# ethernet_hdmi.net
KiCad netlist of a schematic drawn in Altium Designer
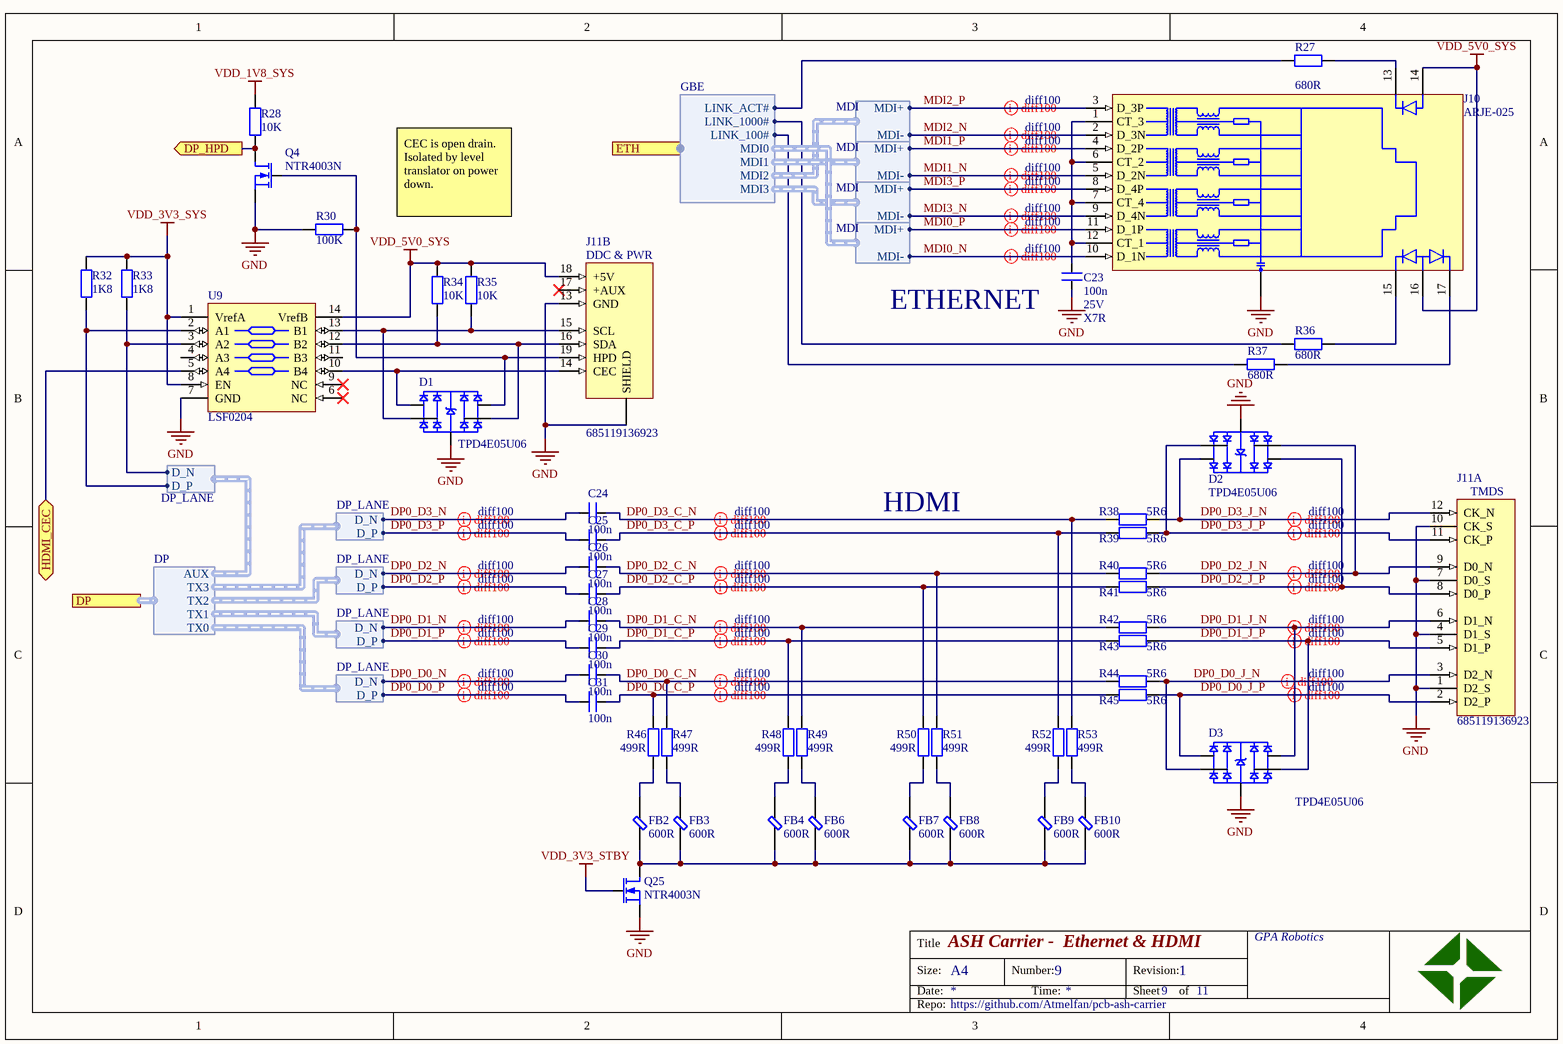
[diagram p0: ethernet_hdmi.SchDoc]

(export (version "E")
  (design (tool "Eeschema 10.0.6"))
  (components
    (comp (ref "C23")
      (value "100n")
      (footprint "C1005[0402]")
      (description "Capacitor")
      (fields (field (name "VOLTAGE") "25V") (field (name "TYPE") "X7R") (field (name "Comment") "cap"))
      (libsource (lib "gpa_passives") (part "cap"))
    )
    (comp (ref "C24")
      (value "100n")
      (footprint "C1005[0402]")
      (description "Capacitor")
      (fields (field (name "VOLTAGE") "25V") (field (name "Comment") "cap"))
      (libsource (lib "gpa_passives") (part "cap"))
    )
    (comp (ref "C25")
      (value "100n")
      (footprint "C1005[0402]")
      (description "Capacitor")
      (fields (field (name "VOLTAGE") "25V") (field (name "Comment") "cap"))
      (libsource (lib "gpa_passives") (part "cap"))
    )
    (comp (ref "C26")
      (value "100n")
      (footprint "C1005[0402]")
      (description "Capacitor")
      (fields (field (name "VOLTAGE") "25V") (field (name "Comment") "cap"))
      (libsource (lib "gpa_passives") (part "cap"))
    )
    (comp (ref "C27")
      (value "100n")
      (footprint "C1005[0402]")
      (description "Capacitor")
      (fields (field (name "VOLTAGE") "25V") (field (name "Comment") "cap"))
      (libsource (lib "gpa_passives") (part "cap"))
    )
    (comp (ref "C28")
      (value "100n")
      (footprint "C1005[0402]")
      (description "Capacitor")
      (fields (field (name "VOLTAGE") "25V") (field (name "Comment") "cap"))
      (libsource (lib "gpa_passives") (part "cap"))
    )
    (comp (ref "C29")
      (value "100n")
      (footprint "C1005[0402]")
      (description "Capacitor")
      (fields (field (name "VOLTAGE") "25V") (field (name "Comment") "cap"))
      (libsource (lib "gpa_passives") (part "cap"))
    )
    (comp (ref "C30")
      (value "100n")
      (footprint "C1005[0402]")
      (description "Capacitor")
      (fields (field (name "VOLTAGE") "25V") (field (name "Comment") "cap"))
      (libsource (lib "gpa_passives") (part "cap"))
    )
    (comp (ref "C31")
      (value "100n")
      (footprint "C1005[0402]")
      (description "Capacitor")
      (fields (field (name "VOLTAGE") "25V") (field (name "Comment") "cap"))
      (libsource (lib "gpa_passives") (part "cap"))
    )
    (comp (ref "D1")
      (value "TPD4E05U06")
      (footprint "TI_PSON50P100X55-10N")
      (libsource (lib "gpa_ti") (part "tpd4e05u06"))
    )
    (comp (ref "D2")
      (value "TPD4E05U06")
      (footprint "TI_PSON50P100X55-10N")
      (libsource (lib "gpa_ti") (part "tpd4e05u06"))
    )
    (comp (ref "D3")
      (value "TPD4E05U06")
      (footprint "TI_PSON50P100X55-10N")
      (libsource (lib "gpa_ti") (part "tpd4e05u06"))
    )
    (comp (ref "FB2")
      (value "600R")
      (footprint "FBC1005X06N")
      (description "Ferrite bead")
      (libsource (lib "gpa_passives") (part "ferrite_bead"))
    )
    (comp (ref "FB3")
      (value "600R")
      (footprint "FBC1005X06N")
      (description "Ferrite bead")
      (libsource (lib "gpa_passives") (part "ferrite_bead"))
    )
    (comp (ref "FB4")
      (value "600R")
      (footprint "FBC1005X06N")
      (description "Ferrite bead")
      (libsource (lib "gpa_passives") (part "ferrite_bead"))
    )
    (comp (ref "FB6")
      (value "600R")
      (footprint "FBC1005X06N")
      (description "Ferrite bead")
      (libsource (lib "gpa_passives") (part "ferrite_bead"))
    )
    (comp (ref "FB7")
      (value "600R")
      (footprint "FBC1005X06N")
      (description "Ferrite bead")
      (libsource (lib "gpa_passives") (part "ferrite_bead"))
    )
    (comp (ref "FB8")
      (value "600R")
      (footprint "FBC1005X06N")
      (description "Ferrite bead")
      (libsource (lib "gpa_passives") (part "ferrite_bead"))
    )
    (comp (ref "FB9")
      (value "600R")
      (footprint "FBC1005X06N")
      (description "Ferrite bead")
      (libsource (lib "gpa_passives") (part "ferrite_bead"))
    )
    (comp (ref "FB10")
      (value "600R")
      (footprint "FBC1005X06N")
      (description "Ferrite bead")
      (libsource (lib "gpa_passives") (part "ferrite_bead"))
    )
    (comp (ref "J10")
      (value "ARJE-025")
      (footprint "abraconn_rj45_arje0025")
      (description "RJ45 with integrated magnetics")
      (libsource (lib "gpa_connectors") (part "geth_wmagnetics"))
    )
    (comp (ref "J11")
      (value "685119136923")
      (footprint "wurth_hdmi_mini")
      (libsource (lib "gpa_connectors") (part "hdmi_mini_c"))
    )
    (comp (ref "Q4")
      (value "NTR4003N")
      (footprint "NCH_SOT95P237X110-3N")
      (libsource (lib "gpa_actives") (part "nch_mosfet"))
    )
    (comp (ref "Q25")
      (value "NTR4003N")
      (footprint "NCH_SOT95P237X110-3N")
      (libsource (lib "gpa_actives") (part "nch_mosfet"))
    )
    (comp (ref "R27")
      (value "680R")
      (footprint "R1005[0402]")
      (description "Resistor")
      (fields (field (name "Comment") "res"))
      (libsource (lib "") (part "res_2"))
    )
    (comp (ref "R28")
      (value "10K")
      (footprint "R1005[0402]")
      (description "Resistor")
      (fields (field (name "Comment") "res"))
      (libsource (lib "") (part "res_1"))
    )
    (comp (ref "R30")
      (value "100K")
      (footprint "R1005[0402]")
      (description "Resistor")
      (fields (field (name "Comment") "res"))
      (libsource (lib "") (part "res_2"))
    )
    (comp (ref "R32")
      (value "1K8")
      (footprint "R1005[0402]")
      (description "Resistor")
      (fields (field (name "Comment") "res"))
      (libsource (lib "") (part "res_1"))
    )
    (comp (ref "R33")
      (value "1K8")
      (footprint "R1005[0402]")
      (description "Resistor")
      (fields (field (name "Comment") "res"))
      (libsource (lib "") (part "res_1"))
    )
    (comp (ref "R34")
      (value "10K")
      (footprint "R1005[0402]")
      (description "Resistor")
      (fields (field (name "Comment") "res"))
      (libsource (lib "") (part "res_1"))
    )
    (comp (ref "R35")
      (value "10K")
      (footprint "R1005[0402]")
      (description "Resistor")
      (fields (field (name "Comment") "res"))
      (libsource (lib "") (part "res_1"))
    )
    (comp (ref "R36")
      (value "680R")
      (footprint "R1005[0402]")
      (description "Resistor")
      (fields (field (name "Comment") "res"))
      (libsource (lib "gpa_passives") (part "res"))
    )
    (comp (ref "R37")
      (value "680R")
      (footprint "R1005[0402]")
      (description "Resistor")
      (fields (field (name "Comment") "res"))
      (libsource (lib "") (part "res_2"))
    )
    (comp (ref "R38")
      (value "5R6")
      (footprint "R1005[0402]")
      (description "Resistor")
      (fields (field (name "Comment") "res"))
      (libsource (lib "gpa_passives") (part "res"))
    )
    (comp (ref "R39")
      (value "5R6")
      (footprint "R1005[0402]")
      (description "Resistor")
      (fields (field (name "Comment") "res"))
      (libsource (lib "gpa_passives") (part "res"))
    )
    (comp (ref "R40")
      (value "5R6")
      (footprint "R1005[0402]")
      (description "Resistor")
      (fields (field (name "Comment") "res"))
      (libsource (lib "gpa_passives") (part "res"))
    )
    (comp (ref "R41")
      (value "5R6")
      (footprint "R1005[0402]")
      (description "Resistor")
      (fields (field (name "Comment") "res"))
      (libsource (lib "gpa_passives") (part "res"))
    )
    (comp (ref "R42")
      (value "5R6")
      (footprint "R1005[0402]")
      (description "Resistor")
      (fields (field (name "Comment") "res"))
      (libsource (lib "gpa_passives") (part "res"))
    )
    (comp (ref "R43")
      (value "5R6")
      (footprint "R1005[0402]")
      (description "Resistor")
      (fields (field (name "Comment") "res"))
      (libsource (lib "gpa_passives") (part "res"))
    )
    (comp (ref "R44")
      (value "5R6")
      (footprint "R1005[0402]")
      (description "Resistor")
      (fields (field (name "Comment") "res"))
      (libsource (lib "gpa_passives") (part "res"))
    )
    (comp (ref "R45")
      (value "5R6")
      (footprint "R1005[0402]")
      (description "Resistor")
      (fields (field (name "Comment") "res"))
      (libsource (lib "gpa_passives") (part "res"))
    )
    (comp (ref "R46")
      (value "499R")
      (footprint "R1005[0402]")
      (description "Resistor")
      (fields (field (name "Comment") "res"))
      (libsource (lib "") (part "res_1"))
    )
    (comp (ref "R47")
      (value "499R")
      (footprint "R1005[0402]")
      (description "Resistor")
      (fields (field (name "Comment") "res"))
      (libsource (lib "") (part "res_1"))
    )
    (comp (ref "R48")
      (value "499R")
      (footprint "R1005[0402]")
      (description "Resistor")
      (fields (field (name "Comment") "res"))
      (libsource (lib "") (part "res_1"))
    )
    (comp (ref "R49")
      (value "499R")
      (footprint "R1005[0402]")
      (description "Resistor")
      (fields (field (name "Comment") "res"))
      (libsource (lib "") (part "res_1"))
    )
    (comp (ref "R50")
      (value "499R")
      (footprint "R1005[0402]")
      (description "Resistor")
      (fields (field (name "Comment") "res"))
      (libsource (lib "") (part "res_1"))
    )
    (comp (ref "R51")
      (value "499R")
      (footprint "R1005[0402]")
      (description "Resistor")
      (fields (field (name "Comment") "res"))
      (libsource (lib "") (part "res_1"))
    )
    (comp (ref "R52")
      (value "499R")
      (footprint "R1005[0402]")
      (description "Resistor")
      (fields (field (name "Comment") "res"))
      (libsource (lib "") (part "res_1"))
    )
    (comp (ref "R53")
      (value "499R")
      (footprint "R1005[0402]")
      (description "Resistor")
      (fields (field (name "Comment") "res"))
      (libsource (lib "") (part "res_1"))
    )
    (comp (ref "U9")
      (value "LSF0204")
      (footprint "TI_TSOP65P640X120-14N")
      (libsource (lib "gpa_ti") (part "lsf0204"))
    )
  )
  (nets
    (net (code "5") (name "/DP0_D0_C_N") (class "Default")
      (node (ref "C30") (pin "1") (pinfunction "1_1") (pintype "passive"))
      (node (ref "R44") (pin "1") (pinfunction "1_1") (pintype "passive"))
      (node (ref "R47") (pin "2") (pinfunction "2_2") (pintype "passive"))
    )
    (net (code "6") (name "/DP0_D0_C_P") (class "Default")
      (node (ref "C31") (pin "1") (pinfunction "1_1") (pintype "passive"))
      (node (ref "R45") (pin "1") (pinfunction "1_1") (pintype "passive"))
      (node (ref "R46") (pin "2") (pinfunction "2_2") (pintype "passive"))
    )
    (net (code "7") (name "/DP0_D0_J_N") (class "Default")
      (node (ref "D3") (pin "4") (pinfunction "D2-_4") (pintype "passive"))
      (node (ref "J11") (pin "3") (pinfunction "D2_N_3") (pintype "input"))
      (node (ref "R44") (pin "2") (pinfunction "2_2") (pintype "passive"))
    )
    (net (code "8") (name "/DP0_D0_J_P") (class "Default")
      (node (ref "D3") (pin "5") (pinfunction "D2+_5") (pintype "passive"))
      (node (ref "J11") (pin "2") (pinfunction "D2_P_2") (pintype "input"))
      (node (ref "R45") (pin "2") (pinfunction "2_2") (pintype "passive"))
    )
    (net (code "9") (name "/DP0_D0_N") (class "Default")
      (node (ref "C30") (pin "2") (pinfunction "2_2") (pintype "passive"))
    )
    (net (code "10") (name "/DP0_D0_P") (class "Default")
      (node (ref "C31") (pin "2") (pinfunction "2_2") (pintype "passive"))
    )
    (net (code "11") (name "/DP0_D1_C_N") (class "Default")
      (node (ref "C28") (pin "1") (pinfunction "1_1") (pintype "passive"))
      (node (ref "R42") (pin "1") (pinfunction "1_1") (pintype "passive"))
      (node (ref "R49") (pin "2") (pinfunction "2_2") (pintype "passive"))
    )
    (net (code "12") (name "/DP0_D1_C_P") (class "Default")
      (node (ref "C29") (pin "1") (pinfunction "1_1") (pintype "passive"))
      (node (ref "R43") (pin "1") (pinfunction "1_1") (pintype "passive"))
      (node (ref "R48") (pin "2") (pinfunction "2_2") (pintype "passive"))
    )
    (net (code "13") (name "/DP0_D1_J_N") (class "Default")
      (node (ref "D3") (pin "1") (pinfunction "D1+_1") (pintype "passive"))
      (node (ref "J11") (pin "6") (pinfunction "D1_N_6") (pintype "input"))
      (node (ref "R42") (pin "2") (pinfunction "2_2") (pintype "passive"))
    )
    (net (code "14") (name "/DP0_D1_J_P") (class "Default")
      (node (ref "D3") (pin "2") (pinfunction "D1-_2") (pintype "passive"))
      (node (ref "J11") (pin "5") (pinfunction "D1_P_5") (pintype "input"))
      (node (ref "R43") (pin "2") (pinfunction "2_2") (pintype "passive"))
    )
    (net (code "15") (name "/DP0_D1_N") (class "Default")
      (node (ref "C28") (pin "2") (pinfunction "2_2") (pintype "passive"))
    )
    (net (code "16") (name "/DP0_D1_P") (class "Default")
      (node (ref "C29") (pin "2") (pinfunction "2_2") (pintype "passive"))
    )
    (net (code "17") (name "/DP0_D2_C_N") (class "Default")
      (node (ref "C26") (pin "1") (pinfunction "1_1") (pintype "passive"))
      (node (ref "R40") (pin "1") (pinfunction "1_1") (pintype "passive"))
      (node (ref "R51") (pin "2") (pinfunction "2_2") (pintype "passive"))
    )
    (net (code "18") (name "/DP0_D2_C_P") (class "Default")
      (node (ref "C27") (pin "1") (pinfunction "1_1") (pintype "passive"))
      (node (ref "R41") (pin "1") (pinfunction "1_1") (pintype "passive"))
      (node (ref "R50") (pin "2") (pinfunction "2_2") (pintype "passive"))
    )
    (net (code "19") (name "/DP0_D2_J_N") (class "Default")
      (node (ref "D2") (pin "2") (pinfunction "D1-_2") (pintype "passive"))
      (node (ref "J11") (pin "9") (pinfunction "D0_N_9") (pintype "input"))
      (node (ref "R40") (pin "2") (pinfunction "2_2") (pintype "passive"))
    )
    (net (code "20") (name "/DP0_D2_J_P") (class "Default")
      (node (ref "D2") (pin "1") (pinfunction "D1+_1") (pintype "passive"))
      (node (ref "J11") (pin "8") (pinfunction "D0_P_8") (pintype "input"))
      (node (ref "R41") (pin "2") (pinfunction "2_2") (pintype "passive"))
    )
    (net (code "21") (name "/DP0_D2_N") (class "Default")
      (node (ref "C26") (pin "2") (pinfunction "2_2") (pintype "passive"))
    )
    (net (code "22") (name "/DP0_D2_P") (class "Default")
      (node (ref "C27") (pin "2") (pinfunction "2_2") (pintype "passive"))
    )
    (net (code "23") (name "/DP0_D3_C_N") (class "Default")
      (node (ref "C24") (pin "1") (pinfunction "1_1") (pintype "passive"))
      (node (ref "R38") (pin "1") (pinfunction "1_1") (pintype "passive"))
      (node (ref "R53") (pin "2") (pinfunction "2_2") (pintype "passive"))
    )
    (net (code "24") (name "/DP0_D3_C_P") (class "Default")
      (node (ref "C25") (pin "1") (pinfunction "1_1") (pintype "passive"))
      (node (ref "R39") (pin "1") (pinfunction "1_1") (pintype "passive"))
      (node (ref "R52") (pin "2") (pinfunction "2_2") (pintype "passive"))
    )
    (net (code "25") (name "/DP0_D3_J_N") (class "Default")
      (node (ref "D2") (pin "5") (pinfunction "D2+_5") (pintype "passive"))
      (node (ref "J11") (pin "12") (pinfunction "CK_N_12") (pintype "input"))
      (node (ref "R38") (pin "2") (pinfunction "2_2") (pintype "passive"))
    )
    (net (code "26") (name "/DP0_D3_J_P") (class "Default")
      (node (ref "D2") (pin "4") (pinfunction "D2-_4") (pintype "passive"))
      (node (ref "J11") (pin "11") (pinfunction "CK_P_11") (pintype "input"))
      (node (ref "R39") (pin "2") (pinfunction "2_2") (pintype "passive"))
    )
    (net (code "27") (name "/DP0_D3_N") (class "Default")
      (node (ref "C24") (pin "2") (pinfunction "2_2") (pintype "passive"))
    )
    (net (code "28") (name "/DP0_D3_P") (class "Default")
      (node (ref "C25") (pin "2") (pinfunction "2_2") (pintype "passive"))
    )
    (net (code "29") (name "/DP_HPD") (class "Default")
      (node (ref "Q4") (pin "D") (pinfunction "D_D") (pintype "passive"))
      (node (ref "R28") (pin "1") (pinfunction "1_1") (pintype "passive"))
    )
    (net (code "32") (name "/HDMI_CEC") (class "Default")
      (node (ref "U9") (pin "5") (pinfunction "A4_5") (pintype "bidirectional"))
    )
    (net (code "33") (name "/LINK_100#") (class "Default")
      (node (ref "R37") (pin "2") (pinfunction "2_2") (pintype "passive"))
    )
    (net (code "34") (name "/LINK_1000#") (class "Default")
      (node (ref "R36") (pin "1") (pinfunction "1_1") (pintype "passive"))
    )
    (net (code "35") (name "/LINK_ACT#") (class "Default")
      (node (ref "R27") (pin "2") (pinfunction "2_2") (pintype "passive"))
    )
    (net (code "36") (name "/MDI0_N") (class "Default")
      (node (ref "J10") (pin "10") (pinfunction "D_1N_10") (pintype "input"))
    )
    (net (code "37") (name "/MDI0_P") (class "Default")
      (node (ref "J10") (pin "11") (pinfunction "D_1P_11") (pintype "input"))
    )
    (net (code "38") (name "/MDI1_N") (class "Default")
      (node (ref "J10") (pin "5") (pinfunction "D_2N_5") (pintype "input"))
    )
    (net (code "39") (name "/MDI1_P") (class "Default")
      (node (ref "J10") (pin "4") (pinfunction "D_2P_4") (pintype "input"))
    )
    (net (code "40") (name "/MDI2_N") (class "Default")
      (node (ref "J10") (pin "2") (pinfunction "D_3N_2") (pintype "input"))
    )
    (net (code "41") (name "/MDI2_P") (class "Default")
      (node (ref "J10") (pin "3") (pinfunction "D_3P_3") (pintype "input"))
    )
    (net (code "42") (name "/MDI3_N") (class "Default")
      (node (ref "J10") (pin "9") (pinfunction "D_4N_9") (pintype "input"))
    )
    (net (code "43") (name "/MDI3_P") (class "Default")
      (node (ref "J10") (pin "8") (pinfunction "D_4P_8") (pintype "input"))
    )
    (net (code "46") (name "GND") (class "Default")
      (node (ref "C23") (pin "1") (pinfunction "1_1") (pintype "passive"))
      (node (ref "D1") (pin "3") (pinfunction "GND_3") (pintype "passive"))
      (node (ref "D2") (pin "3") (pinfunction "GND_3") (pintype "passive"))
      (node (ref "D3") (pin "3") (pinfunction "GND_3") (pintype "passive"))
      (node (ref "J10") (pin "SHIELD") (pinfunction "SHIELD_SHIELD") (pintype "power_in"))
      (node (ref "J11") (pin "1") (pinfunction "D2_S_1") (pintype "power_in"))
      (node (ref "J11") (pin "10") (pinfunction "CK_S_10") (pintype "power_in"))
      (node (ref "J11") (pin "13") (pinfunction "GND_13") (pintype "input"))
      (node (ref "J11") (pin "4") (pinfunction "D1_S_4") (pintype "power_in"))
      (node (ref "J11") (pin "7") (pinfunction "D0_S_7") (pintype "power_in"))
      (node (ref "J11") (pin "SHIELD") (pinfunction "SHIELD_SHIELD") (pintype "passive"))
      (node (ref "Q25") (pin "S") (pinfunction "S_S") (pintype "passive"))
      (node (ref "Q4") (pin "S") (pinfunction "S_S") (pintype "passive"))
      (node (ref "R30") (pin "2") (pinfunction "2_2") (pintype "passive"))
      (node (ref "U9") (pin "7") (pinfunction "GND_7") (pintype "power_in"))
    )
    (net (code "47") (name "Net-(D1-D1+)") (class "Default")
      (node (ref "D1") (pin "1") (pinfunction "D1+_1") (pintype "passive"))
      (node (ref "J11") (pin "14") (pinfunction "CEC_14") (pintype "input"))
      (node (ref "U9") (pin "10") (pinfunction "B4_10") (pintype "bidirectional"))
    )
    (net (code "48") (name "Net-(D1-D1-)") (class "Default")
      (node (ref "D1") (pin "2") (pinfunction "D1-_2") (pintype "passive"))
      (node (ref "J11") (pin "15") (pinfunction "SCL_15") (pintype "input"))
      (node (ref "R35") (pin "1") (pinfunction "1_1") (pintype "passive"))
      (node (ref "U9") (pin "13") (pinfunction "B1_13") (pintype "bidirectional"))
    )
    (net (code "49") (name "Net-(D1-D2+)") (class "Default")
      (node (ref "D1") (pin "5") (pinfunction "D2+_5") (pintype "passive"))
      (node (ref "J11") (pin "19") (pinfunction "HPD_19") (pintype "input"))
      (node (ref "Q4") (pin "G") (pinfunction "G_G") (pintype "passive"))
      (node (ref "R30") (pin "1") (pinfunction "1_1") (pintype "passive"))
    )
    (net (code "50") (name "Net-(D1-D2-)") (class "Default")
      (node (ref "D1") (pin "4") (pinfunction "D2-_4") (pintype "passive"))
      (node (ref "J11") (pin "16") (pinfunction "SDA_16") (pintype "input"))
      (node (ref "R34") (pin "1") (pinfunction "1_1") (pintype "passive"))
      (node (ref "U9") (pin "12") (pinfunction "B2_12") (pintype "bidirectional"))
    )
    (net (code "51") (name "Net-(FB2-Pad2)") (class "Default")
      (node (ref "FB2") (pin "2") (pinfunction "2_2") (pintype "passive"))
      (node (ref "R46") (pin "1") (pinfunction "1_1") (pintype "passive"))
    )
    (net (code "52") (name "Net-(FB3-Pad2)") (class "Default")
      (node (ref "FB3") (pin "2") (pinfunction "2_2") (pintype "passive"))
      (node (ref "R47") (pin "1") (pinfunction "1_1") (pintype "passive"))
    )
    (net (code "53") (name "Net-(FB4-Pad2)") (class "Default")
      (node (ref "FB4") (pin "2") (pinfunction "2_2") (pintype "passive"))
      (node (ref "R48") (pin "1") (pinfunction "1_1") (pintype "passive"))
    )
    (net (code "54") (name "Net-(FB6-Pad2)") (class "Default")
      (node (ref "FB6") (pin "2") (pinfunction "2_2") (pintype "passive"))
      (node (ref "R49") (pin "1") (pinfunction "1_1") (pintype "passive"))
    )
    (net (code "55") (name "Net-(FB7-Pad2)") (class "Default")
      (node (ref "FB7") (pin "2") (pinfunction "2_2") (pintype "passive"))
      (node (ref "R50") (pin "1") (pinfunction "1_1") (pintype "passive"))
    )
    (net (code "56") (name "Net-(FB8-Pad2)") (class "Default")
      (node (ref "FB8") (pin "2") (pinfunction "2_2") (pintype "passive"))
      (node (ref "R51") (pin "1") (pinfunction "1_1") (pintype "passive"))
    )
    (net (code "57") (name "Net-(FB9-Pad2)") (class "Default")
      (node (ref "FB9") (pin "2") (pinfunction "2_2") (pintype "passive"))
      (node (ref "R52") (pin "1") (pinfunction "1_1") (pintype "passive"))
    )
    (net (code "58") (name "Net-(FB10-Pad1)") (class "Default")
      (node (ref "FB10") (pin "1") (pinfunction "1_1") (pintype "passive"))
      (node (ref "FB2") (pin "1") (pinfunction "1_1") (pintype "passive"))
      (node (ref "FB3") (pin "1") (pinfunction "1_1") (pintype "passive"))
      (node (ref "FB4") (pin "1") (pinfunction "1_1") (pintype "passive"))
      (node (ref "FB6") (pin "1") (pinfunction "1_1") (pintype "passive"))
      (node (ref "FB7") (pin "1") (pinfunction "1_1") (pintype "passive"))
      (node (ref "FB8") (pin "1") (pinfunction "1_1") (pintype "passive"))
      (node (ref "FB9") (pin "1") (pinfunction "1_1") (pintype "passive"))
      (node (ref "Q25") (pin "D") (pinfunction "D_D") (pintype "passive"))
    )
    (net (code "59") (name "Net-(FB10-Pad2)") (class "Default")
      (node (ref "FB10") (pin "2") (pinfunction "2_2") (pintype "passive"))
      (node (ref "R53") (pin "1") (pinfunction "1_1") (pintype "passive"))
    )
    (net (code "60") (name "Net-(J10-CT_1)") (class "Default")
      (node (ref "C23") (pin "2") (pinfunction "2_2") (pintype "passive"))
      (node (ref "J10") (pin "1") (pinfunction "CT_3_1") (pintype "passive"))
      (node (ref "J10") (pin "12") (pinfunction "CT_1_12") (pintype "passive"))
      (node (ref "J10") (pin "6") (pinfunction "CT_2_6") (pintype "passive"))
      (node (ref "J10") (pin "7") (pinfunction "CT_4_7") (pintype "passive"))
    )
    (net (code "61") (name "Net-(J10-Pad13)") (class "Default")
      (node (ref "J10") (pin "13") (pinfunction "13_13") (pintype "passive"))
      (node (ref "R27") (pin "1") (pinfunction "1_1") (pintype "passive"))
    )
    (net (code "62") (name "Net-(J10-Pad15)") (class "Default")
      (node (ref "J10") (pin "15") (pinfunction "15_15") (pintype "passive"))
      (node (ref "R36") (pin "2") (pinfunction "2_2") (pintype "passive"))
    )
    (net (code "63") (name "Net-(J10-Pad17)") (class "Default")
      (node (ref "J10") (pin "17") (pinfunction "17_17") (pintype "passive"))
      (node (ref "R37") (pin "1") (pinfunction "1_1") (pintype "passive"))
    )
    (net (code "64") (name "Net-(U9-A1)") (class "Default")
      (node (ref "R32") (pin "1") (pinfunction "1_1") (pintype "passive"))
      (node (ref "U9") (pin "2") (pinfunction "A1_2") (pintype "bidirectional"))
    )
    (net (code "65") (name "Net-(U9-A2)") (class "Default")
      (node (ref "R33") (pin "1") (pinfunction "1_1") (pintype "passive"))
      (node (ref "U9") (pin "3") (pinfunction "A2_3") (pintype "bidirectional"))
    )
    (net (code "66") (name "VDD_1V8_SYS") (class "Default")
      (node (ref "R28") (pin "2") (pinfunction "2_2") (pintype "passive"))
    )
    (net (code "67") (name "VDD_3V3_STBY") (class "Default")
      (node (ref "Q25") (pin "G") (pinfunction "G_G") (pintype "passive"))
    )
    (net (code "68") (name "VDD_3V3_SYS") (class "Default")
      (node (ref "R32") (pin "2") (pinfunction "2_2") (pintype "passive"))
      (node (ref "R33") (pin "2") (pinfunction "2_2") (pintype "passive"))
      (node (ref "U9") (pin "1") (pinfunction "VrefA_1") (pintype "power_in"))
      (node (ref "U9") (pin "8") (pinfunction "EN_8") (pintype "input"))
    )
    (net (code "69") (name "VDD_5V0_SYS") (class "Default")
      (node (ref "J10") (pin "14") (pinfunction "14_14") (pintype "passive"))
      (node (ref "J10") (pin "16") (pinfunction "16_16") (pintype "passive"))
      (node (ref "J11") (pin "18") (pinfunction "+5V_18") (pintype "input"))
      (node (ref "R34") (pin "2") (pinfunction "2_2") (pintype "passive"))
      (node (ref "R35") (pin "2") (pinfunction "2_2") (pintype "passive"))
      (node (ref "U9") (pin "14") (pinfunction "VrefB_14") (pintype "power_in"))
    )
    (net (code "70") (name "unconnected-(J11B-+AUX-Pad17)") (class "Default")
      (node (ref "J11") (pin "17") (pinfunction "+AUX_17") (pintype "input+no_connect"))
    )
    (net (code "71") (name "unconnected-(U9-A3-Pad4)") (class "Default")
      (node (ref "U9") (pin "4") (pinfunction "A3_4") (pintype "bidirectional"))
    )
    (net (code "72") (name "unconnected-(U9-B3-Pad11)") (class "Default")
      (node (ref "U9") (pin "11") (pinfunction "B3_11") (pintype "bidirectional"))
    )
    (net (code "73") (name "unconnected-(U9-NC-Pad6)") (class "Default")
      (node (ref "U9") (pin "6") (pinfunction "NC_6") (pintype "input+no_connect"))
    )
    (net (code "74") (name "unconnected-(U9-NC-Pad9)") (class "Default")
      (node (ref "U9") (pin "9") (pinfunction "NC_9") (pintype "input+no_connect"))
    )
  )
)
